# ArduinoAdapter.net
KiCad netlist of a schematic drawn in EAGLE
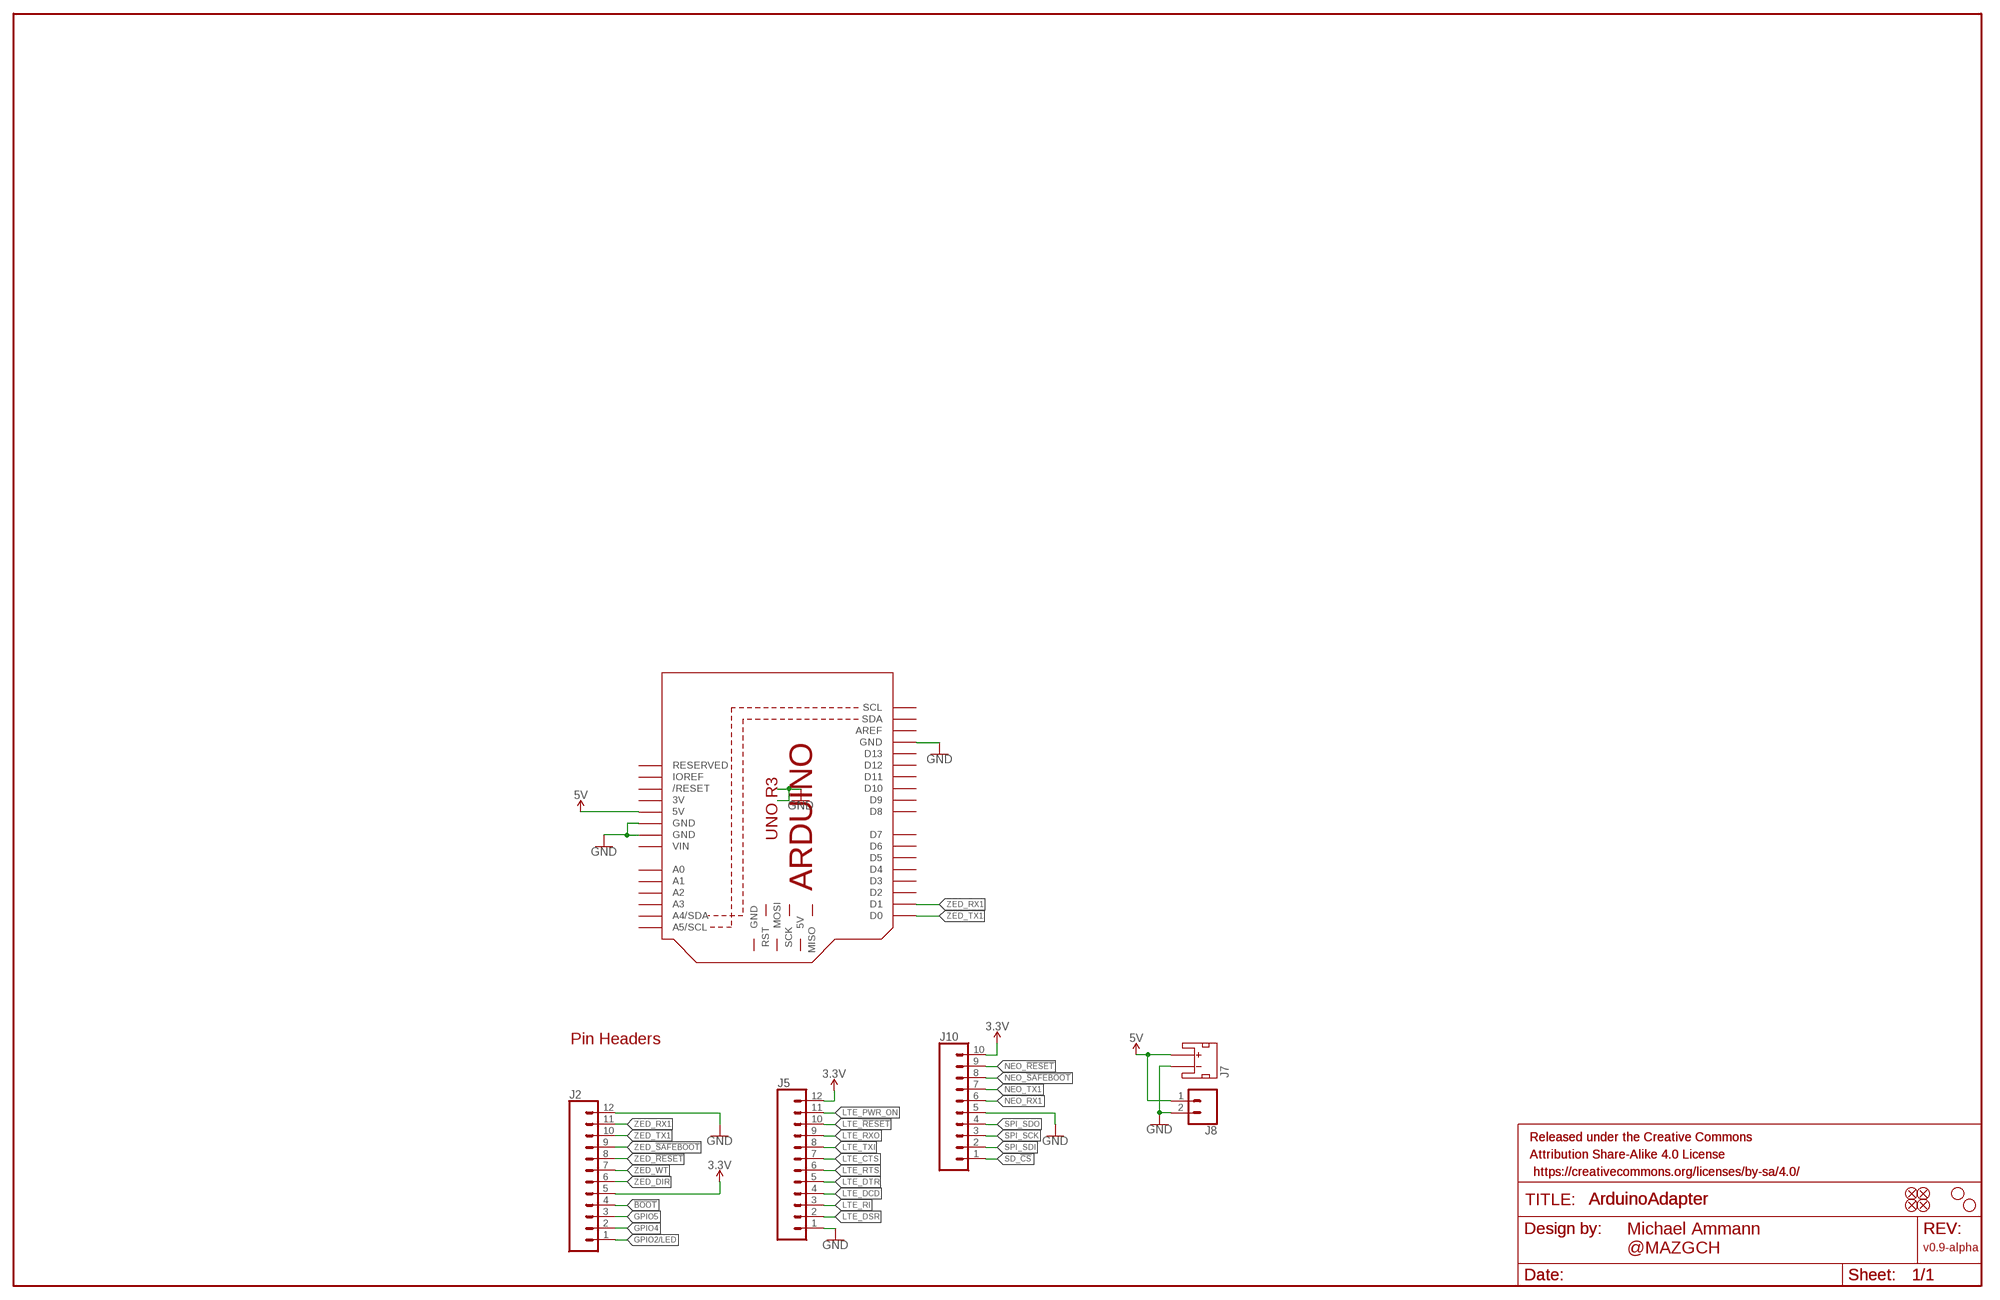
[diagram p0: schematic, sheet 1]

(export (version "E")
  (design (tool "Eeschema 10.0.6"))
  (components
    (comp (ref "FD1")
      (value "FIDUCIALUFIDUCIAL")
      (footprint "eagle-import:FIDUCIAL-MICRO")
      (libsource (lib "eagle-import") (part "FIDUCIALUFIDUCIAL"))
    )
    (comp (ref "FD2")
      (value "FIDUCIALUFIDUCIAL")
      (footprint "eagle-import:FIDUCIAL-MICRO")
      (libsource (lib "eagle-import") (part "FIDUCIALUFIDUCIAL"))
    )
    (comp (ref "FD3")
      (value "FIDUCIALUFIDUCIAL")
      (footprint "eagle-import:FIDUCIAL-MICRO")
      (libsource (lib "eagle-import") (part "FIDUCIALUFIDUCIAL"))
    )
    (comp (ref "FD4")
      (value "FIDUCIALUFIDUCIAL")
      (footprint "eagle-import:FIDUCIAL-MICRO")
      (libsource (lib "eagle-import") (part "FIDUCIALUFIDUCIAL"))
    )
    (comp (ref "FRAME1")
      (value "FRAME-LEDGER")
      (footprint "eagle-import:CREATIVE_COMMONS")
      (libsource (lib "eagle-import") (part "FRAME-LEDGER"))
    )
    (comp (ref "FRAME2")
      (value "FRAME-LEDGER")
      (footprint "eagle-import:CREATIVE_COMMONS")
      (libsource (lib "eagle-import") (part "FRAME-LEDGER"))
    )
    (comp (ref "H1")
      (value "STAND-OFFTIGHT")
      (footprint "eagle-import:STAND-OFF-TIGHT")
      (libsource (lib "eagle-import") (part "STAND-OFFTIGHT"))
    )
    (comp (ref "H4")
      (value "STAND-OFFTIGHT")
      (footprint "eagle-import:STAND-OFF-TIGHT")
      (libsource (lib "eagle-import") (part "STAND-OFFTIGHT"))
    )
    (comp (ref "J2")
      (value "CONN_12NO_SILK")
      (footprint "eagle-import:1X12_NO_SILK")
      (libsource (lib "eagle-import") (part "CONN_12NO_SILK"))
    )
    (comp (ref "J5")
      (value "CONN_12NO_SILK")
      (footprint "eagle-import:1X12_NO_SILK")
      (libsource (lib "eagle-import") (part "CONN_12NO_SILK"))
    )
    (comp (ref "J7")
      (value "JST_2MM_MALE")
      (footprint "eagle-import:JST-2-SMD")
      (libsource (lib "eagle-import") (part "JST_2MM_MALE"))
    )
    (comp (ref "J8")
      (value "CONN_021X02_NO_SILK")
      (footprint "eagle-import:1X02_NO_SILK")
      (libsource (lib "eagle-import") (part "CONN_021X02_NO_SILK"))
    )
    (comp (ref "J10")
      (value "CONN_10NO_SILK_PTH_FEMALE")
      (footprint "eagle-import:1X10_NO_SILK")
      (libsource (lib "eagle-import") (part "CONN_10NO_SILK_PTH_FEMALE"))
    )
    (comp (ref "M1")
      (value "ARDUINO_R3_ICSP")
      (footprint "eagle-import:ARDUINOR3_ICSP")
      (libsource (lib "eagle-import") (part "ARDUINO_R3_ICSP"))
    )
  )
  (nets
    (net (code "1") (name "/3V") (class "Default")
      (node (ref "M1") (pin "3V") (pinfunction "3V_3V") (pintype "power_in"))
    )
    (net (code "2") (name "/LTE_~{RESET}") (class "Default")
      (node (ref "J5") (pin "10") (pinfunction "10_10") (pintype "passive"))
    )
    (net (code "3") (name "/NEO_~{RESET}") (class "Default")
      (node (ref "J10") (pin "9") (pinfunction "9_9") (pintype "passive"))
    )
    (net (code "4") (name "/NEO_~{SAFEBOOT}") (class "Default")
      (node (ref "J10") (pin "8") (pinfunction "8_8") (pintype "passive"))
    )
    (net (code "5") (name "/SD_~{CS}") (class "Default")
      (node (ref "J10") (pin "1") (pinfunction "1_1") (pintype "passive"))
    )
    (net (code "6") (name "/VIN") (class "Default")
      (node (ref "M1") (pin "VIN") (pinfunction "VIN_VIN") (pintype "power_in"))
    )
    (net (code "7") (name "/ZED_~{RESET}") (class "Default")
      (node (ref "J2") (pin "8") (pinfunction "8_8") (pintype "passive"))
    )
    (net (code "8") (name "/ZED_~{SAFEBOOT}") (class "Default")
      (node (ref "J2") (pin "9") (pinfunction "9_9") (pintype "passive"))
    )
    (net (code "9") (name "/~{BOOT}") (class "Default")
      (node (ref "J2") (pin "4") (pinfunction "4_4") (pintype "passive"))
    )
    (net (code "10") (name "3.3V") (class "Default")
      (node (ref "J10") (pin "10") (pinfunction "10_10") (pintype "passive"))
      (node (ref "J2") (pin "5") (pinfunction "5_5") (pintype "passive"))
      (node (ref "J5") (pin "12") (pinfunction "12_12") (pintype "passive"))
    )
    (net (code "11") (name "5V") (class "Default")
      (node (ref "J7") (pin "2") (pinfunction "+_2") (pintype "bidirectional"))
      (node (ref "J8") (pin "1") (pinfunction "1_1") (pintype "passive"))
      (node (ref "M1") (pin "5V") (pinfunction "5V_5V") (pintype "power_in"))
    )
    (net (code "12") (name "GND") (class "Default")
      (node (ref "J10") (pin "5") (pinfunction "5_5") (pintype "passive"))
      (node (ref "J2") (pin "12") (pinfunction "12_12") (pintype "passive"))
      (node (ref "J5") (pin "1") (pinfunction "1_1") (pintype "passive"))
      (node (ref "J7") (pin "1") (pinfunction "-_1") (pintype "bidirectional"))
      (node (ref "J8") (pin "2") (pinfunction "2_2") (pintype "passive"))
      (node (ref "M1") (pin "GND") (pinfunction "GND_GND") (pintype "power_in"))
      (node (ref "M1") (pin "GND@1") (pinfunction "GND_GND@1") (pintype "power_in"))
      (node (ref "M1") (pin "GND@3") (pinfunction "GND_GND@3") (pintype "power_in"))
    )
    (net (code "13") (name "GPIO2{slash}LED") (class "Default")
      (node (ref "J2") (pin "1") (pinfunction "1_1") (pintype "passive"))
    )
    (net (code "14") (name "GPIO4") (class "Default")
      (node (ref "J2") (pin "2") (pinfunction "2_2") (pintype "passive"))
    )
    (net (code "15") (name "GPIO5") (class "Default")
      (node (ref "J2") (pin "3") (pinfunction "3_3") (pintype "passive"))
    )
    (net (code "16") (name "LTE_CTS") (class "Default")
      (node (ref "J5") (pin "7") (pinfunction "7_7") (pintype "passive"))
    )
    (net (code "17") (name "LTE_DCD") (class "Default")
      (node (ref "J5") (pin "4") (pinfunction "4_4") (pintype "passive"))
    )
    (net (code "18") (name "LTE_DSR") (class "Default")
      (node (ref "J5") (pin "2") (pinfunction "2_2") (pintype "passive"))
    )
    (net (code "19") (name "LTE_DTR") (class "Default")
      (node (ref "J5") (pin "5") (pinfunction "5_5") (pintype "passive"))
    )
    (net (code "20") (name "LTE_PWR_ON") (class "Default")
      (node (ref "J5") (pin "11") (pinfunction "11_11") (pintype "passive"))
    )
    (net (code "21") (name "LTE_RI") (class "Default")
      (node (ref "J5") (pin "3") (pinfunction "3_3") (pintype "passive"))
    )
    (net (code "22") (name "LTE_RTS") (class "Default")
      (node (ref "J5") (pin "6") (pinfunction "6_6") (pintype "passive"))
    )
    (net (code "23") (name "LTE_RXO") (class "Default")
      (node (ref "J5") (pin "9") (pinfunction "9_9") (pintype "passive"))
    )
    (net (code "24") (name "LTE_TXI") (class "Default")
      (node (ref "J5") (pin "8") (pinfunction "8_8") (pintype "passive"))
    )
    (net (code "25") (name "NEO_RX1") (class "Default")
      (node (ref "J10") (pin "6") (pinfunction "6_6") (pintype "passive"))
    )
    (net (code "26") (name "NEO_TX1") (class "Default")
      (node (ref "J10") (pin "7") (pinfunction "7_7") (pintype "passive"))
    )
    (net (code "27") (name "SPI_SCK") (class "Default")
      (node (ref "J10") (pin "3") (pinfunction "3_3") (pintype "passive"))
    )
    (net (code "28") (name "SPI_SDI") (class "Default")
      (node (ref "J10") (pin "2") (pinfunction "2_2") (pintype "passive"))
    )
    (net (code "29") (name "SPI_SDO") (class "Default")
      (node (ref "J10") (pin "4") (pinfunction "4_4") (pintype "passive"))
    )
    (net (code "30") (name "ZED_DIR") (class "Default")
      (node (ref "J2") (pin "6") (pinfunction "6_6") (pintype "passive"))
    )
    (net (code "31") (name "ZED_RX1") (class "Default")
      (node (ref "J2") (pin "11") (pinfunction "11_11") (pintype "passive"))
      (node (ref "M1") (pin "D1") (pinfunction "D1_D1") (pintype "bidirectional"))
    )
    (net (code "32") (name "ZED_TX1") (class "Default")
      (node (ref "J2") (pin "10") (pinfunction "10_10") (pintype "passive"))
      (node (ref "M1") (pin "D0") (pinfunction "D0_D0") (pintype "bidirectional"))
    )
    (net (code "33") (name "ZED_WT") (class "Default")
      (node (ref "J2") (pin "7") (pinfunction "7_7") (pintype "passive"))
    )
    (net (code "34") (name "unconnected-(J7-PAD1-PadNC1)") (class "Default")
      (node (ref "J7") (pin "NC1") (pinfunction "PAD1_NC1") (pintype "bidirectional"))
    )
    (net (code "35") (name "unconnected-(J7-PAD2-PadNC2)") (class "Default")
      (node (ref "J7") (pin "NC2") (pinfunction "PAD2_NC2") (pintype "bidirectional"))
    )
    (net (code "36") (name "unconnected-(M1-5V-Pad5V_ICSP)") (class "Default")
      (node (ref "M1") (pin "5V_ICSP") (pinfunction "5V_5V_ICSP") (pintype "passive"))
    )
    (net (code "37") (name "unconnected-(M1-A4{slash}SDA-PadA4)") (class "Default")
      (node (ref "M1") (pin "A4") (pinfunction "A4/SDA_A4") (pintype "bidirectional"))
    )
    (net (code "38") (name "unconnected-(M1-A5{slash}SCL-PadA5)") (class "Default")
      (node (ref "M1") (pin "A5") (pinfunction "A5/SCL_A5") (pintype "bidirectional"))
    )
    (net (code "39") (name "unconnected-(M1-GND-PadGND@2)") (class "Default")
      (node (ref "M1") (pin "GND@2") (pinfunction "GND_GND@2") (pintype "passive"))
    )
    (net (code "40") (name "unconnected-(M1-PadA0)") (class "Default")
      (node (ref "M1") (pin "A0") (pinfunction "A0_A0") (pintype "bidirectional"))
    )
    (net (code "41") (name "unconnected-(M1-PadA1)") (class "Default")
      (node (ref "M1") (pin "A1") (pinfunction "A1_A1") (pintype "bidirectional"))
    )
    (net (code "42") (name "unconnected-(M1-PadA2)") (class "Default")
      (node (ref "M1") (pin "A2") (pinfunction "A2_A2") (pintype "bidirectional"))
    )
    (net (code "43") (name "unconnected-(M1-PadA3)") (class "Default")
      (node (ref "M1") (pin "A3") (pinfunction "A3_A3") (pintype "bidirectional"))
    )
    (net (code "44") (name "unconnected-(M1-PadAREF)") (class "Default")
      (node (ref "M1") (pin "AREF") (pinfunction "AREF_AREF") (pintype "bidirectional"))
    )
    (net (code "45") (name "unconnected-(M1-PadD2)") (class "Default")
      (node (ref "M1") (pin "D2") (pinfunction "D2_D2") (pintype "bidirectional"))
    )
    (net (code "46") (name "unconnected-(M1-PadD3)") (class "Default")
      (node (ref "M1") (pin "D3") (pinfunction "D3_D3") (pintype "bidirectional"))
    )
    (net (code "47") (name "unconnected-(M1-PadD4)") (class "Default")
      (node (ref "M1") (pin "D4") (pinfunction "D4_D4") (pintype "bidirectional"))
    )
    (net (code "48") (name "unconnected-(M1-PadD5)") (class "Default")
      (node (ref "M1") (pin "D5") (pinfunction "D5_D5") (pintype "bidirectional"))
    )
    (net (code "49") (name "unconnected-(M1-PadD6)") (class "Default")
      (node (ref "M1") (pin "D6") (pinfunction "D6_D6") (pintype "bidirectional"))
    )
    (net (code "50") (name "unconnected-(M1-PadD7)") (class "Default")
      (node (ref "M1") (pin "D7") (pinfunction "D7_D7") (pintype "bidirectional"))
    )
    (net (code "51") (name "unconnected-(M1-PadD8)") (class "Default")
      (node (ref "M1") (pin "D8") (pinfunction "D8_D8") (pintype "bidirectional"))
    )
    (net (code "52") (name "unconnected-(M1-PadD9)") (class "Default")
      (node (ref "M1") (pin "D9") (pinfunction "D9_D9") (pintype "bidirectional"))
    )
    (net (code "53") (name "unconnected-(M1-PadD10)") (class "Default")
      (node (ref "M1") (pin "D10") (pinfunction "D10_D10") (pintype "bidirectional"))
    )
    (net (code "54") (name "unconnected-(M1-PadD11)") (class "Default")
      (node (ref "M1") (pin "D11") (pinfunction "D11_D11") (pintype "bidirectional"))
    )
    (net (code "55") (name "unconnected-(M1-PadD12)") (class "Default")
      (node (ref "M1") (pin "D12") (pinfunction "D12_D12") (pintype "bidirectional"))
    )
    (net (code "56") (name "unconnected-(M1-PadD13)") (class "Default")
      (node (ref "M1") (pin "D13") (pinfunction "D13_D13") (pintype "bidirectional"))
    )
    (net (code "57") (name "unconnected-(M1-PadIOREF)") (class "Default")
      (node (ref "M1") (pin "IOREF") (pinfunction "IOREF_IOREF") (pintype "output"))
    )
    (net (code "58") (name "unconnected-(M1-PadMISO)") (class "Default")
      (node (ref "M1") (pin "MISO") (pinfunction "MISO_MISO") (pintype "passive"))
    )
    (net (code "59") (name "unconnected-(M1-PadMOSI)") (class "Default")
      (node (ref "M1") (pin "MOSI") (pinfunction "MOSI_MOSI") (pintype "passive"))
    )
    (net (code "60") (name "unconnected-(M1-PadRESERVED)") (class "Default")
      (node (ref "M1") (pin "RESERVED") (pinfunction "RESERVED_RESERVED") (pintype "no_connect"))
    )
    (net (code "61") (name "unconnected-(M1-PadSCK)") (class "Default")
      (node (ref "M1") (pin "SCK") (pinfunction "SCK_SCK") (pintype "passive"))
    )
    (net (code "62") (name "unconnected-(M1-PadSCL)") (class "Default")
      (node (ref "M1") (pin "SCL") (pinfunction "SCL_SCL") (pintype "bidirectional"))
    )
    (net (code "63") (name "unconnected-(M1-PadSDA)") (class "Default")
      (node (ref "M1") (pin "SDA") (pinfunction "SDA_SDA") (pintype "bidirectional"))
    )
    (net (code "64") (name "unconnected-(M1-RST-PadRESET_ICSP)") (class "Default")
      (node (ref "M1") (pin "RESET_ICSP") (pinfunction "RST_RESET_ICSP") (pintype "passive"))
    )
    (net (code "65") (name "unconnected-(M1-{slash}RESET-PadRESET)") (class "Default")
      (node (ref "M1") (pin "RESET") (pinfunction "/RESET_RESET") (pintype "bidirectional"))
    )
  )
)
